# RoverWing-cover-nocut-V5.net
KiCad netlist of a schematic drawn in EAGLE
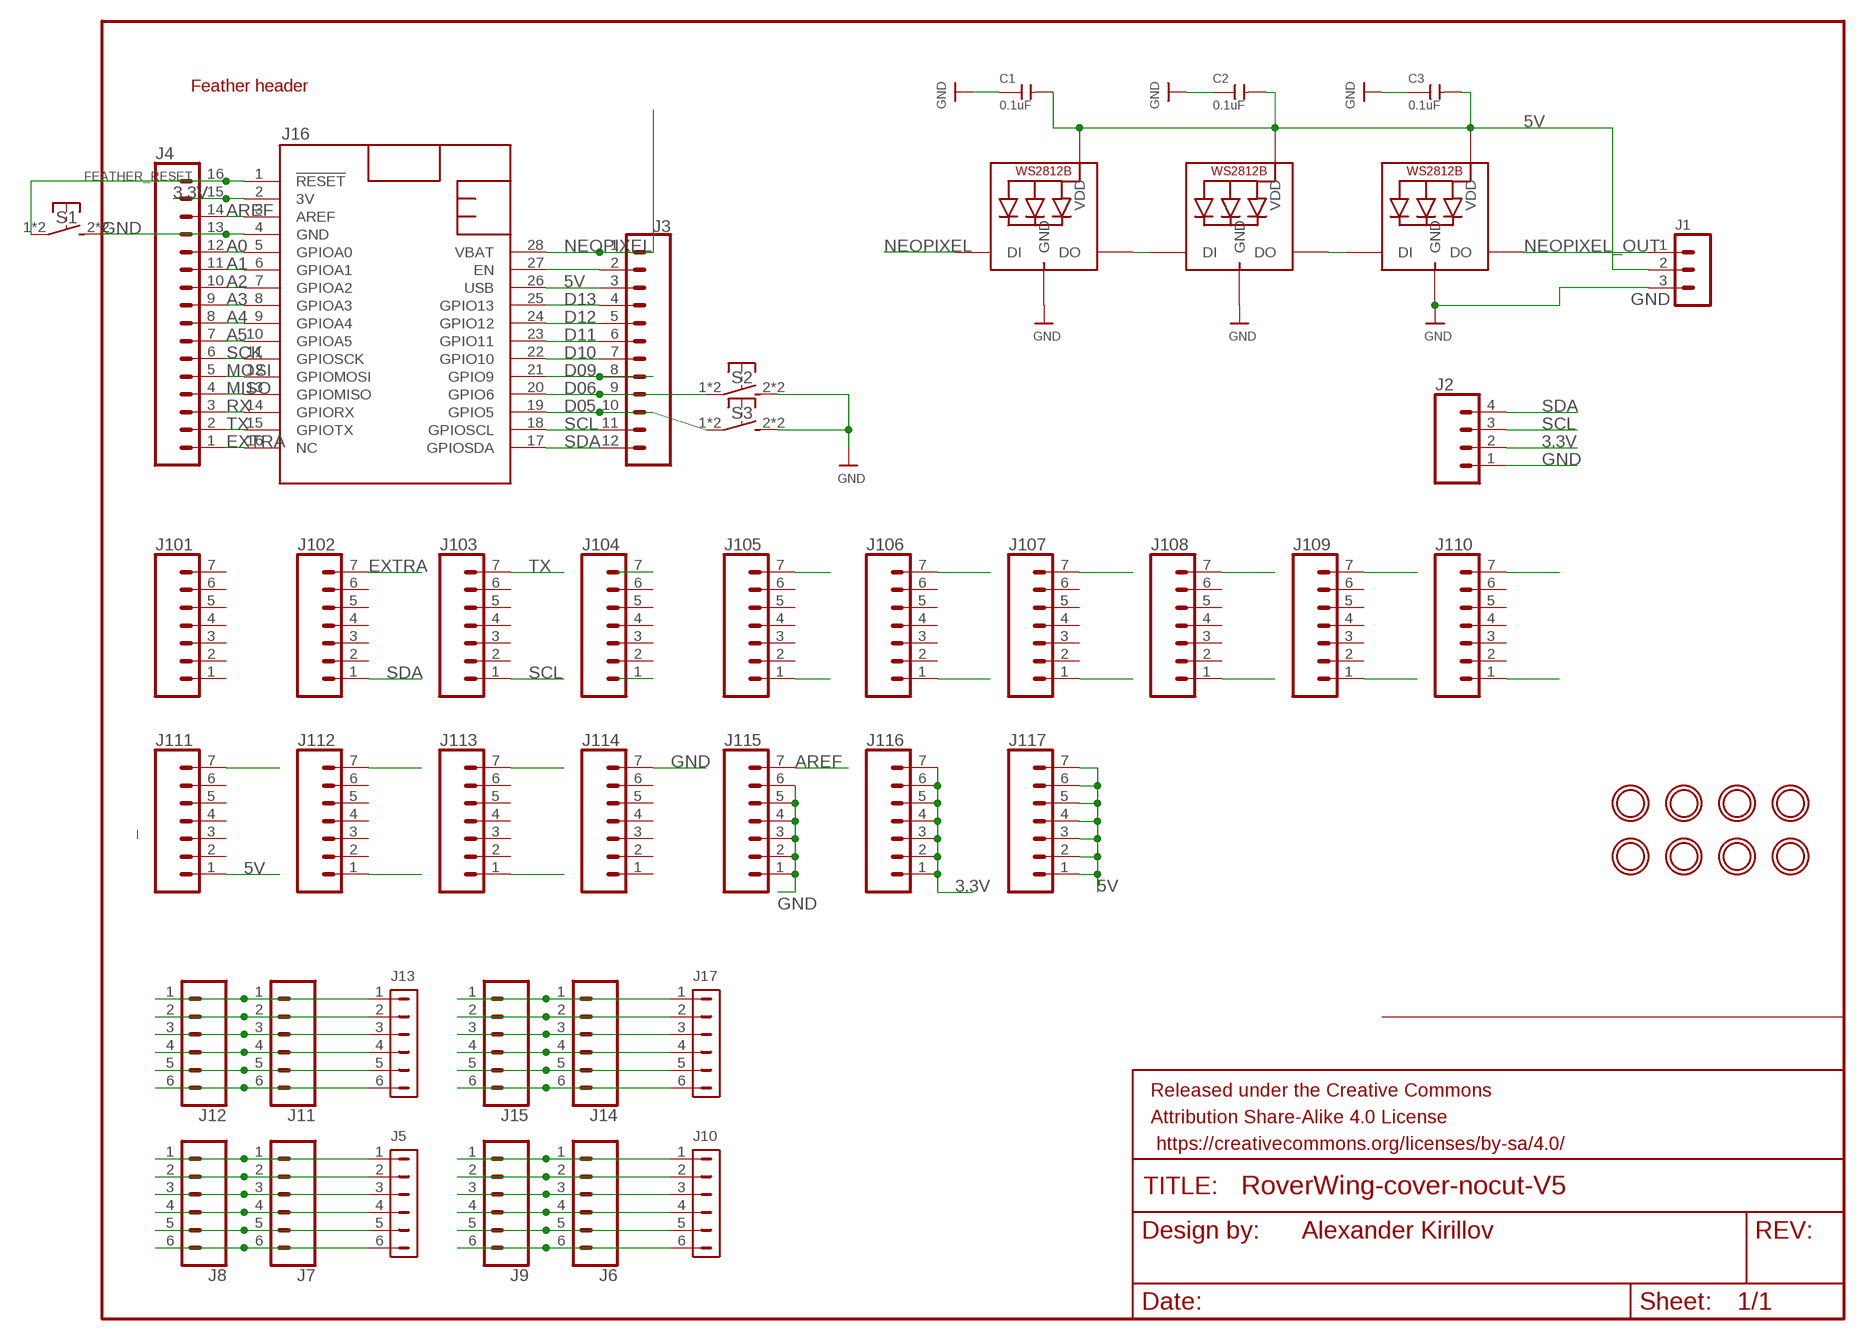
[diagram p0: schematic, sheet 1]

(export (version "E")
  (design (tool "Eeschema 10.0.6"))
  (components
    (comp (ref "C1")
      (value "0.1uF")
      (footprint "eagle-import:C0805")
      (libsource (lib "eagle-import") (part "CAP-CERAMIC-SMD-0805"))
    )
    (comp (ref "C2")
      (value "0.1uF")
      (footprint "eagle-import:C0805")
      (libsource (lib "eagle-import") (part "CAP-CERAMIC-SMD-0805"))
    )
    (comp (ref "C3")
      (value "0.1uF")
      (footprint "eagle-import:C0805")
      (libsource (lib "eagle-import") (part "CAP-CERAMIC-SMD-0805"))
    )
    (comp (ref "FRAME2")
      (value "FRAME-LETTERNO_PACKAGE")
      (footprint "eagle-import:DUMMY")
      (fields (field (name "DESIGNER") "Nobody"))
      (libsource (lib "eagle-import") (part "FRAME-LETTERNO_PACKAGE"))
    )
    (comp (ref "J1")
      (value "HEADER-PH-3PSIDEENTRY")
      (footprint "eagle-import:S3B-PH-K")
      (fields (field (name "PARTNO") "S3B-PH-K-S(LF)(SN)"))
      (libsource (lib "eagle-import") (part "HEADER-PH-3PSIDEENTRY"))
    )
    (comp (ref "J2")
      (value "CONN_04")
      (footprint "eagle-import:1X04")
      (libsource (lib "eagle-import") (part "CONN_04"))
    )
    (comp (ref "J3")
      (value "CONN_12NO_SILK")
      (footprint "eagle-import:1X12_NO_SILK")
      (libsource (lib "eagle-import") (part "CONN_12NO_SILK"))
    )
    (comp (ref "J4")
      (value "CONN_161X16_NO_SILK")
      (footprint "eagle-import:1X16_NO_SILK")
      (libsource (lib "eagle-import") (part "CONN_161X16_NO_SILK"))
    )
    (comp (ref "J5")
      (value "HEADER-PH-6PSIDEENTRY")
      (footprint "eagle-import:S6B-PH-K")
      (libsource (lib "eagle-import") (part "HEADER-PH-6PSIDEENTRY"))
    )
    (comp (ref "J6")
      (value "CONN_06NO_SILK_NO_POP")
      (footprint "eagle-import:1X06_NO_SILK")
      (libsource (lib "eagle-import") (part "CONN_06NO_SILK_NO_POP"))
    )
    (comp (ref "J7")
      (value "CONN_06NO_SILK_NO_POP")
      (footprint "eagle-import:1X06_NO_SILK")
      (libsource (lib "eagle-import") (part "CONN_06NO_SILK_NO_POP"))
    )
    (comp (ref "J8")
      (value "CONN_06NO_SILK_NO_POP")
      (footprint "eagle-import:1X06_NO_SILK")
      (libsource (lib "eagle-import") (part "CONN_06NO_SILK_NO_POP"))
    )
    (comp (ref "J9")
      (value "CONN_06NO_SILK_NO_POP")
      (footprint "eagle-import:1X06_NO_SILK")
      (libsource (lib "eagle-import") (part "CONN_06NO_SILK_NO_POP"))
    )
    (comp (ref "J10")
      (value "HEADER-PH-6PSIDEENTRY")
      (footprint "eagle-import:S6B-PH-K")
      (libsource (lib "eagle-import") (part "HEADER-PH-6PSIDEENTRY"))
    )
    (comp (ref "J11")
      (value "CONN_06NO_SILK_NO_POP")
      (footprint "eagle-import:1X06_NO_SILK")
      (libsource (lib "eagle-import") (part "CONN_06NO_SILK_NO_POP"))
    )
    (comp (ref "J12")
      (value "CONN_06NO_SILK_NO_POP")
      (footprint "eagle-import:1X06_NO_SILK")
      (libsource (lib "eagle-import") (part "CONN_06NO_SILK_NO_POP"))
    )
    (comp (ref "J13")
      (value "HEADER-PH-6PSIDEENTRY")
      (footprint "eagle-import:S6B-PH-K")
      (libsource (lib "eagle-import") (part "HEADER-PH-6PSIDEENTRY"))
    )
    (comp (ref "J14")
      (value "CONN_06NO_SILK_NO_POP")
      (footprint "eagle-import:1X06_NO_SILK")
      (libsource (lib "eagle-import") (part "CONN_06NO_SILK_NO_POP"))
    )
    (comp (ref "J15")
      (value "CONN_06NO_SILK_NO_POP")
      (footprint "eagle-import:1X06_NO_SILK")
      (libsource (lib "eagle-import") (part "CONN_06NO_SILK_NO_POP"))
    )
    (comp (ref "J16")
      (value "FEATHERWING_NODIM")
      (footprint "eagle-import:FEATHERWING_DIM")
      (libsource (lib "eagle-import") (part "FEATHERWING_NODIM"))
    )
    (comp (ref "J17")
      (value "HEADER-PH-6PSIDEENTRY")
      (footprint "eagle-import:S6B-PH-K")
      (libsource (lib "eagle-import") (part "HEADER-PH-6PSIDEENTRY"))
    )
    (comp (ref "J101")
      (value "CONN_07NO_SILK")
      (footprint "eagle-import:1X07_NO_SILK")
      (libsource (lib "eagle-import") (part "CONN_07NO_SILK"))
    )
    (comp (ref "J102")
      (value "CONN_07NO_SILK")
      (footprint "eagle-import:1X07_NO_SILK")
      (libsource (lib "eagle-import") (part "CONN_07NO_SILK"))
    )
    (comp (ref "J103")
      (value "CONN_07NO_SILK")
      (footprint "eagle-import:1X07_NO_SILK")
      (libsource (lib "eagle-import") (part "CONN_07NO_SILK"))
    )
    (comp (ref "J104")
      (value "CONN_07NO_SILK")
      (footprint "eagle-import:1X07_NO_SILK")
      (libsource (lib "eagle-import") (part "CONN_07NO_SILK"))
    )
    (comp (ref "J105")
      (value "CONN_07NO_SILK")
      (footprint "eagle-import:1X07_NO_SILK")
      (libsource (lib "eagle-import") (part "CONN_07NO_SILK"))
    )
    (comp (ref "J106")
      (value "CONN_07NO_SILK")
      (footprint "eagle-import:1X07_NO_SILK")
      (libsource (lib "eagle-import") (part "CONN_07NO_SILK"))
    )
    (comp (ref "J107")
      (value "CONN_07NO_SILK")
      (footprint "eagle-import:1X07_NO_SILK")
      (libsource (lib "eagle-import") (part "CONN_07NO_SILK"))
    )
    (comp (ref "J108")
      (value "CONN_07NO_SILK")
      (footprint "eagle-import:1X07_NO_SILK")
      (libsource (lib "eagle-import") (part "CONN_07NO_SILK"))
    )
    (comp (ref "J109")
      (value "CONN_07NO_SILK")
      (footprint "eagle-import:1X07_NO_SILK")
      (libsource (lib "eagle-import") (part "CONN_07NO_SILK"))
    )
    (comp (ref "J110")
      (value "CONN_07NO_SILK")
      (footprint "eagle-import:1X07_NO_SILK")
      (libsource (lib "eagle-import") (part "CONN_07NO_SILK"))
    )
    (comp (ref "J111")
      (value "CONN_07NO_SILK")
      (footprint "eagle-import:1X07_NO_SILK")
      (libsource (lib "eagle-import") (part "CONN_07NO_SILK"))
    )
    (comp (ref "J112")
      (value "CONN_07NO_SILK")
      (footprint "eagle-import:1X07_NO_SILK")
      (libsource (lib "eagle-import") (part "CONN_07NO_SILK"))
    )
    (comp (ref "J113")
      (value "CONN_07NO_SILK")
      (footprint "eagle-import:1X07_NO_SILK")
      (libsource (lib "eagle-import") (part "CONN_07NO_SILK"))
    )
    (comp (ref "J114")
      (value "CONN_07NO_SILK")
      (footprint "eagle-import:1X07_NO_SILK")
      (libsource (lib "eagle-import") (part "CONN_07NO_SILK"))
    )
    (comp (ref "J115")
      (value "CONN_07NO_SILK")
      (footprint "eagle-import:1X07_NO_SILK")
      (libsource (lib "eagle-import") (part "CONN_07NO_SILK"))
    )
    (comp (ref "J116")
      (value "CONN_07NO_SILK")
      (footprint "eagle-import:1X07_NO_SILK")
      (libsource (lib "eagle-import") (part "CONN_07NO_SILK"))
    )
    (comp (ref "J117")
      (value "CONN_07NO_SILK")
      (footprint "eagle-import:1X07_NO_SILK")
      (libsource (lib "eagle-import") (part "CONN_07NO_SILK"))
    )
    (comp (ref "LED1")
      (value "WS2812B5050")
      (footprint "eagle-import:WS2812B")
      (libsource (lib "eagle-import") (part "WS2812B5050"))
    )
    (comp (ref "LED2")
      (value "WS2812B5050")
      (footprint "eagle-import:WS2812B")
      (libsource (lib "eagle-import") (part "WS2812B5050"))
    )
    (comp (ref "LED3")
      (value "WS2812B5050")
      (footprint "eagle-import:WS2812B")
      (libsource (lib "eagle-import") (part "WS2812B5050"))
    )
    (comp (ref "S1")
      (value "SW-TACTILE-4.5X4.5_SMD")
      (footprint "eagle-import:TL3305")
      (libsource (lib "eagle-import") (part "SW-TACTILE-4.5X4.5_SMD"))
    )
    (comp (ref "S2")
      (value "SW-TACTILE-4.5X4.5_SMD")
      (footprint "eagle-import:TL3305")
      (libsource (lib "eagle-import") (part "SW-TACTILE-4.5X4.5_SMD"))
    )
    (comp (ref "S3")
      (value "SW-TACTILE-4.5X4.5_SMD")
      (footprint "eagle-import:TL3305")
      (libsource (lib "eagle-import") (part "SW-TACTILE-4.5X4.5_SMD"))
    )
    (comp (ref "U$3")
      (value "MOUNTINGHOLE3.0_NPH")
      (footprint "eagle-import:MOUNTINGHOLE_3.0_NPH")
      (libsource (lib "eagle-import") (part "MOUNTINGHOLE3.0_NPH"))
    )
    (comp (ref "U$4")
      (value "MOUNTINGHOLE3.0_NPH")
      (footprint "eagle-import:MOUNTINGHOLE_3.0_NPH")
      (libsource (lib "eagle-import") (part "MOUNTINGHOLE3.0_NPH"))
    )
    (comp (ref "U$14")
      (value "MOUNTINGHOLE3.0_NPH")
      (footprint "eagle-import:MOUNTINGHOLE_3.0_NPH")
      (libsource (lib "eagle-import") (part "MOUNTINGHOLE3.0_NPH"))
    )
    (comp (ref "U$15")
      (value "MOUNTINGHOLE3.0_NPH")
      (footprint "eagle-import:MOUNTINGHOLE_3.0_NPH")
      (libsource (lib "eagle-import") (part "MOUNTINGHOLE3.0_NPH"))
    )
    (comp (ref "U$24")
      (value "MOUNTINGHOLE3.0_NPH")
      (footprint "eagle-import:MOUNTINGHOLE_3.0_NPH")
      (libsource (lib "eagle-import") (part "MOUNTINGHOLE3.0_NPH"))
    )
    (comp (ref "U$25")
      (value "MOUNTINGHOLE3.0_NPH")
      (footprint "eagle-import:MOUNTINGHOLE_3.0_NPH")
      (libsource (lib "eagle-import") (part "MOUNTINGHOLE3.0_NPH"))
    )
    (comp (ref "U$26")
      (value "MOUNTINGHOLE3.0_NPH")
      (footprint "eagle-import:MOUNTINGHOLE_3.0_NPH")
      (libsource (lib "eagle-import") (part "MOUNTINGHOLE3.0_NPH"))
    )
    (comp (ref "U$27")
      (value "MOUNTINGHOLE3.0_NPH")
      (footprint "eagle-import:MOUNTINGHOLE_3.0_NPH")
      (libsource (lib "eagle-import") (part "MOUNTINGHOLE3.0_NPH"))
    )
  )
  (nets
    (net (code "1") (name "/3.3V") (class "Default")
      (node (ref "J116") (pin "1") (pinfunction "1_1") (pintype "passive"))
      (node (ref "J116") (pin "2") (pinfunction "2_2") (pintype "passive"))
      (node (ref "J116") (pin "3") (pinfunction "3_3") (pintype "passive"))
      (node (ref "J116") (pin "4") (pinfunction "4_4") (pintype "passive"))
      (node (ref "J116") (pin "5") (pinfunction "5_5") (pintype "passive"))
      (node (ref "J116") (pin "6") (pinfunction "6_6") (pintype "passive"))
      (node (ref "J116") (pin "7") (pinfunction "7_7") (pintype "passive"))
      (node (ref "J16") (pin "2") (pinfunction "3V_2") (pintype "power_in"))
      (node (ref "J2") (pin "2") (pinfunction "2_2") (pintype "passive"))
      (node (ref "J4") (pin "15") (pinfunction "15_15") (pintype "passive"))
    )
    (net (code "2") (name "/5V") (class "Default")
      (node (ref "C1") (pin "2") (pinfunction "2_2") (pintype "passive"))
      (node (ref "C2") (pin "2") (pinfunction "2_2") (pintype "passive"))
      (node (ref "C3") (pin "2") (pinfunction "2_2") (pintype "passive"))
      (node (ref "J1") (pin "2") (pinfunction "2_2") (pintype "passive"))
      (node (ref "J111") (pin "1") (pinfunction "1_1") (pintype "passive"))
      (node (ref "J117") (pin "1") (pinfunction "1_1") (pintype "passive"))
      (node (ref "J117") (pin "2") (pinfunction "2_2") (pintype "passive"))
      (node (ref "J117") (pin "3") (pinfunction "3_3") (pintype "passive"))
      (node (ref "J117") (pin "4") (pinfunction "4_4") (pintype "passive"))
      (node (ref "J117") (pin "5") (pinfunction "5_5") (pintype "passive"))
      (node (ref "J117") (pin "6") (pinfunction "6_6") (pintype "passive"))
      (node (ref "J117") (pin "7") (pinfunction "7_7") (pintype "passive"))
      (node (ref "J16") (pin "26") (pinfunction "USB_26") (pintype "power_in"))
      (node (ref "J3") (pin "3") (pinfunction "3_3") (pintype "passive"))
      (node (ref "LED1") (pin "1-VDD") (pinfunction "VDD_1-VDD") (pintype "power_in"))
      (node (ref "LED2") (pin "1-VDD") (pinfunction "VDD_1-VDD") (pintype "power_in"))
      (node (ref "LED3") (pin "1-VDD") (pinfunction "VDD_1-VDD") (pintype "power_in"))
    )
    (net (code "3") (name "/A0") (class "Default")
      (node (ref "J113") (pin "7") (pinfunction "7_7") (pintype "passive"))
      (node (ref "J16") (pin "5") (pinfunction "GPIOA0_5") (pintype "bidirectional"))
      (node (ref "J4") (pin "12") (pinfunction "12_12") (pintype "passive"))
    )
    (net (code "4") (name "/A1") (class "Default")
      (node (ref "J112") (pin "7") (pinfunction "7_7") (pintype "passive"))
      (node (ref "J16") (pin "6") (pinfunction "GPIOA1_6") (pintype "bidirectional"))
      (node (ref "J4") (pin "11") (pinfunction "11_11") (pintype "passive"))
    )
    (net (code "5") (name "/A2") (class "Default")
      (node (ref "J111") (pin "7") (pinfunction "7_7") (pintype "passive"))
      (node (ref "J16") (pin "7") (pinfunction "GPIOA2_7") (pintype "bidirectional"))
      (node (ref "J4") (pin "10") (pinfunction "10_10") (pintype "passive"))
    )
    (net (code "6") (name "/A3") (class "Default")
      (node (ref "J110") (pin "7") (pinfunction "7_7") (pintype "passive"))
      (node (ref "J16") (pin "8") (pinfunction "GPIOA3_8") (pintype "bidirectional"))
      (node (ref "J4") (pin "9") (pinfunction "9_9") (pintype "passive"))
    )
    (net (code "7") (name "/A4") (class "Default")
      (node (ref "J109") (pin "7") (pinfunction "7_7") (pintype "passive"))
      (node (ref "J16") (pin "9") (pinfunction "GPIOA4_9") (pintype "bidirectional"))
      (node (ref "J4") (pin "8") (pinfunction "8_8") (pintype "passive"))
    )
    (net (code "8") (name "/A5") (class "Default")
      (node (ref "J108") (pin "7") (pinfunction "7_7") (pintype "passive"))
      (node (ref "J16") (pin "10") (pinfunction "GPIOA5_10") (pintype "bidirectional"))
      (node (ref "J4") (pin "7") (pinfunction "7_7") (pintype "passive"))
    )
    (net (code "9") (name "/AREF") (class "Default")
      (node (ref "J115") (pin "7") (pinfunction "7_7") (pintype "passive"))
      (node (ref "J16") (pin "3") (pinfunction "AREF_3") (pintype "passive"))
      (node (ref "J4") (pin "14") (pinfunction "14_14") (pintype "passive"))
    )
    (net (code "10") (name "/D05") (class "Default")
      (node (ref "J104") (pin "1") (pinfunction "1_1") (pintype "passive"))
      (node (ref "J16") (pin "19") (pinfunction "GPIO5_19") (pintype "bidirectional"))
      (node (ref "J3") (pin "10") (pinfunction "10_10") (pintype "passive"))
      (node (ref "S3") (pin "1") (pinfunction "P1_1") (pintype "passive"))
      (node (ref "S3") (pin "4") (pinfunction "P1_4") (pintype "passive"))
    )
    (net (code "11") (name "/D06") (class "Default")
      (node (ref "J105") (pin "1") (pinfunction "1_1") (pintype "passive"))
      (node (ref "J16") (pin "20") (pinfunction "GPIO6_20") (pintype "bidirectional"))
      (node (ref "J3") (pin "9") (pinfunction "9_9") (pintype "passive"))
      (node (ref "S2") (pin "1") (pinfunction "P1_1") (pintype "passive"))
      (node (ref "S2") (pin "4") (pinfunction "P1_4") (pintype "passive"))
    )
    (net (code "12") (name "/D09") (class "Default")
      (node (ref "J106") (pin "1") (pinfunction "1_1") (pintype "passive"))
      (node (ref "J16") (pin "21") (pinfunction "GPIO9_21") (pintype "bidirectional"))
      (node (ref "J3") (pin "8") (pinfunction "8_8") (pintype "passive"))
    )
    (net (code "13") (name "/D10") (class "Default")
      (node (ref "J107") (pin "1") (pinfunction "1_1") (pintype "passive"))
      (node (ref "J16") (pin "22") (pinfunction "GPIO10_22") (pintype "bidirectional"))
      (node (ref "J3") (pin "7") (pinfunction "7_7") (pintype "passive"))
    )
    (net (code "14") (name "/D11") (class "Default")
      (node (ref "J108") (pin "1") (pinfunction "1_1") (pintype "passive"))
      (node (ref "J16") (pin "23") (pinfunction "GPIO11_23") (pintype "bidirectional"))
      (node (ref "J3") (pin "6") (pinfunction "6_6") (pintype "passive"))
    )
    (net (code "15") (name "/D12") (class "Default")
      (node (ref "J109") (pin "1") (pinfunction "1_1") (pintype "passive"))
      (node (ref "J16") (pin "24") (pinfunction "GPIO12_24") (pintype "bidirectional"))
      (node (ref "J3") (pin "5") (pinfunction "5_5") (pintype "passive"))
    )
    (net (code "16") (name "/D13") (class "Default")
      (node (ref "J110") (pin "1") (pinfunction "1_1") (pintype "passive"))
      (node (ref "J16") (pin "25") (pinfunction "GPIO13_25") (pintype "bidirectional"))
      (node (ref "J3") (pin "4") (pinfunction "4_4") (pintype "passive"))
    )
    (net (code "17") (name "/EXTRA") (class "Default")
      (node (ref "J102") (pin "7") (pinfunction "7_7") (pintype "passive"))
      (node (ref "J16") (pin "16") (pinfunction "NC_16") (pintype "passive"))
      (node (ref "J4") (pin "1") (pinfunction "1_1") (pintype "passive"))
    )
    (net (code "18") (name "/FEATHER_RESET") (class "Default")
      (node (ref "J16") (pin "1") (pinfunction "~{RESET}_1") (pintype "input"))
      (node (ref "J4") (pin "16") (pinfunction "16_16") (pintype "passive"))
      (node (ref "S1") (pin "1") (pinfunction "P1_1") (pintype "passive"))
      (node (ref "S1") (pin "4") (pinfunction "P1_4") (pintype "passive"))
    )
    (net (code "19") (name "/MISO") (class "Default")
      (node (ref "J105") (pin "7") (pinfunction "7_7") (pintype "passive"))
      (node (ref "J16") (pin "13") (pinfunction "GPIOMISO_13") (pintype "bidirectional"))
      (node (ref "J4") (pin "4") (pinfunction "4_4") (pintype "passive"))
    )
    (net (code "20") (name "/MOSI") (class "Default")
      (node (ref "J106") (pin "7") (pinfunction "7_7") (pintype "passive"))
      (node (ref "J16") (pin "12") (pinfunction "GPIOMOSI_12") (pintype "bidirectional"))
      (node (ref "J4") (pin "5") (pinfunction "5_5") (pintype "passive"))
    )
    (net (code "21") (name "/N$37") (class "Default")
      (node (ref "J112") (pin "1") (pinfunction "1_1") (pintype "passive"))
      (node (ref "J16") (pin "27") (pinfunction "EN_27") (pintype "passive"))
      (node (ref "J3") (pin "2") (pinfunction "2_2") (pintype "passive"))
    )
    (net (code "22") (name "/NEOPIXEL") (class "Default")
      (node (ref "J16") (pin "28") (pinfunction "VBAT_28") (pintype "power_in"))
      (node (ref "J3") (pin "1") (pinfunction "1_1") (pintype "passive"))
      (node (ref "LED1") (pin "4-DIN") (pinfunction "DI_4-DIN") (pintype "input"))
    )
    (net (code "23") (name "/NEOPIXEL_OUT") (class "Default")
      (node (ref "J1") (pin "1") (pinfunction "1_1") (pintype "passive"))
      (node (ref "LED3") (pin "2-DOUT") (pinfunction "DO_2-DOUT") (pintype "output"))
    )
    (net (code "24") (name "/RX") (class "Default")
      (node (ref "J104") (pin "7") (pinfunction "7_7") (pintype "passive"))
      (node (ref "J16") (pin "14") (pinfunction "GPIORX_14") (pintype "bidirectional"))
      (node (ref "J4") (pin "3") (pinfunction "3_3") (pintype "passive"))
    )
    (net (code "25") (name "/SCK") (class "Default")
      (node (ref "J107") (pin "7") (pinfunction "7_7") (pintype "passive"))
      (node (ref "J16") (pin "11") (pinfunction "GPIOSCK_11") (pintype "bidirectional"))
      (node (ref "J4") (pin "6") (pinfunction "6_6") (pintype "passive"))
    )
    (net (code "26") (name "/SCL") (class "Default")
      (node (ref "J103") (pin "1") (pinfunction "1_1") (pintype "passive"))
      (node (ref "J16") (pin "18") (pinfunction "GPIOSCL_18") (pintype "bidirectional"))
      (node (ref "J2") (pin "3") (pinfunction "3_3") (pintype "passive"))
      (node (ref "J3") (pin "11") (pinfunction "11_11") (pintype "passive"))
    )
    (net (code "27") (name "/SDA") (class "Default")
      (node (ref "J102") (pin "1") (pinfunction "1_1") (pintype "passive"))
      (node (ref "J16") (pin "17") (pinfunction "GPIOSDA_17") (pintype "bidirectional"))
      (node (ref "J2") (pin "4") (pinfunction "4_4") (pintype "passive"))
      (node (ref "J3") (pin "12") (pinfunction "12_12") (pintype "passive"))
    )
    (net (code "28") (name "/TX") (class "Default")
      (node (ref "J103") (pin "7") (pinfunction "7_7") (pintype "passive"))
      (node (ref "J16") (pin "15") (pinfunction "GPIOTX_15") (pintype "bidirectional"))
      (node (ref "J4") (pin "2") (pinfunction "2_2") (pintype "passive"))
    )
    (net (code "29") (name "GND") (class "Default")
      (node (ref "C1") (pin "1") (pinfunction "1_1") (pintype "passive"))
      (node (ref "C2") (pin "1") (pinfunction "1_1") (pintype "passive"))
      (node (ref "C3") (pin "1") (pinfunction "1_1") (pintype "passive"))
      (node (ref "J1") (pin "3") (pinfunction "3_3") (pintype "passive"))
      (node (ref "J114") (pin "7") (pinfunction "7_7") (pintype "passive"))
      (node (ref "J115") (pin "1") (pinfunction "1_1") (pintype "passive"))
      (node (ref "J115") (pin "2") (pinfunction "2_2") (pintype "passive"))
      (node (ref "J115") (pin "3") (pinfunction "3_3") (pintype "passive"))
      (node (ref "J115") (pin "4") (pinfunction "4_4") (pintype "passive"))
      (node (ref "J115") (pin "5") (pinfunction "5_5") (pintype "passive"))
      (node (ref "J115") (pin "6") (pinfunction "6_6") (pintype "passive"))
      (node (ref "J16") (pin "4") (pinfunction "GND_4") (pintype "power_in"))
      (node (ref "J2") (pin "1") (pinfunction "1_1") (pintype "passive"))
      (node (ref "J4") (pin "13") (pinfunction "13_13") (pintype "passive"))
      (node (ref "LED1") (pin "3-GND") (pinfunction "GND_3-GND") (pintype "power_in"))
      (node (ref "LED2") (pin "3-GND") (pinfunction "GND_3-GND") (pintype "power_in"))
      (node (ref "LED3") (pin "3-GND") (pinfunction "GND_3-GND") (pintype "power_in"))
      (node (ref "S1") (pin "2") (pinfunction "S1_2") (pintype "passive"))
      (node (ref "S1") (pin "3") (pinfunction "S1_3") (pintype "passive"))
      (node (ref "S2") (pin "2") (pinfunction "S1_2") (pintype "passive"))
      (node (ref "S2") (pin "3") (pinfunction "S1_3") (pintype "passive"))
      (node (ref "S3") (pin "2") (pinfunction "S1_2") (pintype "passive"))
      (node (ref "S3") (pin "3") (pinfunction "S1_3") (pintype "passive"))
    )
    (net (code "30") (name "Net-(J5-Pad1)") (class "Default")
      (node (ref "J5") (pin "1") (pinfunction "1_1") (pintype "passive"))
      (node (ref "J7") (pin "1") (pinfunction "1_1") (pintype "passive"))
      (node (ref "J8") (pin "1") (pinfunction "1_1") (pintype "passive"))
    )
    (net (code "31") (name "Net-(J5-Pad2)") (class "Default")
      (node (ref "J5") (pin "2") (pinfunction "2_2") (pintype "passive"))
      (node (ref "J7") (pin "2") (pinfunction "2_2") (pintype "passive"))
      (node (ref "J8") (pin "2") (pinfunction "2_2") (pintype "passive"))
    )
    (net (code "32") (name "Net-(J5-Pad3)") (class "Default")
      (node (ref "J5") (pin "3") (pinfunction "3_3") (pintype "passive"))
      (node (ref "J7") (pin "3") (pinfunction "3_3") (pintype "passive"))
      (node (ref "J8") (pin "3") (pinfunction "3_3") (pintype "passive"))
    )
    (net (code "33") (name "Net-(J5-Pad4)") (class "Default")
      (node (ref "J5") (pin "4") (pinfunction "4_4") (pintype "passive"))
      (node (ref "J7") (pin "4") (pinfunction "4_4") (pintype "passive"))
      (node (ref "J8") (pin "4") (pinfunction "4_4") (pintype "passive"))
    )
    (net (code "34") (name "Net-(J5-Pad5)") (class "Default")
      (node (ref "J5") (pin "5") (pinfunction "5_5") (pintype "passive"))
      (node (ref "J7") (pin "5") (pinfunction "5_5") (pintype "passive"))
      (node (ref "J8") (pin "5") (pinfunction "5_5") (pintype "passive"))
    )
    (net (code "35") (name "Net-(J5-Pad6)") (class "Default")
      (node (ref "J5") (pin "6") (pinfunction "6_6") (pintype "passive"))
      (node (ref "J7") (pin "6") (pinfunction "6_6") (pintype "passive"))
      (node (ref "J8") (pin "6") (pinfunction "6_6") (pintype "passive"))
    )
    (net (code "36") (name "Net-(J10-Pad1)") (class "Default")
      (node (ref "J10") (pin "1") (pinfunction "1_1") (pintype "passive"))
      (node (ref "J6") (pin "1") (pinfunction "1_1") (pintype "passive"))
      (node (ref "J9") (pin "1") (pinfunction "1_1") (pintype "passive"))
    )
    (net (code "37") (name "Net-(J10-Pad2)") (class "Default")
      (node (ref "J10") (pin "2") (pinfunction "2_2") (pintype "passive"))
      (node (ref "J6") (pin "2") (pinfunction "2_2") (pintype "passive"))
      (node (ref "J9") (pin "2") (pinfunction "2_2") (pintype "passive"))
    )
    (net (code "38") (name "Net-(J10-Pad3)") (class "Default")
      (node (ref "J10") (pin "3") (pinfunction "3_3") (pintype "passive"))
      (node (ref "J6") (pin "3") (pinfunction "3_3") (pintype "passive"))
      (node (ref "J9") (pin "3") (pinfunction "3_3") (pintype "passive"))
    )
    (net (code "39") (name "Net-(J10-Pad4)") (class "Default")
      (node (ref "J10") (pin "4") (pinfunction "4_4") (pintype "passive"))
      (node (ref "J6") (pin "4") (pinfunction "4_4") (pintype "passive"))
      (node (ref "J9") (pin "4") (pinfunction "4_4") (pintype "passive"))
    )
    (net (code "40") (name "Net-(J10-Pad5)") (class "Default")
      (node (ref "J10") (pin "5") (pinfunction "5_5") (pintype "passive"))
      (node (ref "J6") (pin "5") (pinfunction "5_5") (pintype "passive"))
      (node (ref "J9") (pin "5") (pinfunction "5_5") (pintype "passive"))
    )
    (net (code "41") (name "Net-(J10-Pad6)") (class "Default")
      (node (ref "J10") (pin "6") (pinfunction "6_6") (pintype "passive"))
      (node (ref "J6") (pin "6") (pinfunction "6_6") (pintype "passive"))
      (node (ref "J9") (pin "6") (pinfunction "6_6") (pintype "passive"))
    )
    (net (code "42") (name "Net-(J11-Pad1)") (class "Default")
      (node (ref "J11") (pin "1") (pinfunction "1_1") (pintype "passive"))
      (node (ref "J12") (pin "1") (pinfunction "1_1") (pintype "passive"))
      (node (ref "J13") (pin "1") (pinfunction "1_1") (pintype "passive"))
    )
    (net (code "43") (name "Net-(J11-Pad2)") (class "Default")
      (node (ref "J11") (pin "2") (pinfunction "2_2") (pintype "passive"))
      (node (ref "J12") (pin "2") (pinfunction "2_2") (pintype "passive"))
      (node (ref "J13") (pin "2") (pinfunction "2_2") (pintype "passive"))
    )
    (net (code "44") (name "Net-(J11-Pad3)") (class "Default")
      (node (ref "J11") (pin "3") (pinfunction "3_3") (pintype "passive"))
      (node (ref "J12") (pin "3") (pinfunction "3_3") (pintype "passive"))
      (node (ref "J13") (pin "3") (pinfunction "3_3") (pintype "passive"))
    )
    (net (code "45") (name "Net-(J11-Pad4)") (class "Default")
      (node (ref "J11") (pin "4") (pinfunction "4_4") (pintype "passive"))
      (node (ref "J12") (pin "4") (pinfunction "4_4") (pintype "passive"))
      (node (ref "J13") (pin "4") (pinfunction "4_4") (pintype "passive"))
    )
    (net (code "46") (name "Net-(J11-Pad5)") (class "Default")
      (node (ref "J11") (pin "5") (pinfunction "5_5") (pintype "passive"))
      (node (ref "J12") (pin "5") (pinfunction "5_5") (pintype "passive"))
      (node (ref "J13") (pin "5") (pinfunction "5_5") (pintype "passive"))
    )
    (net (code "47") (name "Net-(J11-Pad6)") (class "Default")
      (node (ref "J11") (pin "6") (pinfunction "6_6") (pintype "passive"))
      (node (ref "J12") (pin "6") (pinfunction "6_6") (pintype "passive"))
      (node (ref "J13") (pin "6") (pinfunction "6_6") (pintype "passive"))
    )
    (net (code "48") (name "Net-(J14-Pad1)") (class "Default")
      (node (ref "J14") (pin "1") (pinfunction "1_1") (pintype "passive"))
      (node (ref "J15") (pin "1") (pinfunction "1_1") (pintype "passive"))
      (node (ref "J17") (pin "1") (pinfunction "1_1") (pintype "passive"))
    )
    (net (code "49") (name "Net-(J14-Pad2)") (class "Default")
      (node (ref "J14") (pin "2") (pinfunction "2_2") (pintype "passive"))
      (node (ref "J15") (pin "2") (pinfunction "2_2") (pintype "passive"))
      (node (ref "J17") (pin "2") (pinfunction "2_2") (pintype "passive"))
    )
    (net (code "50") (name "Net-(J14-Pad3)") (class "Default")
      (node (ref "J14") (pin "3") (pinfunction "3_3") (pintype "passive"))
      (node (ref "J15") (pin "3") (pinfunction "3_3") (pintype "passive"))
      (node (ref "J17") (pin "3") (pinfunction "3_3") (pintype "passive"))
    )
    (net (code "51") (name "Net-(J14-Pad4)") (class "Default")
      (node (ref "J14") (pin "4") (pinfunction "4_4") (pintype "passive"))
      (node (ref "J15") (pin "4") (pinfunction "4_4") (pintype "passive"))
      (node (ref "J17") (pin "4") (pinfunction "4_4") (pintype "passive"))
    )
    (net (code "52") (name "Net-(J14-Pad5)") (class "Default")
      (node (ref "J14") (pin "5") (pinfunction "5_5") (pintype "passive"))
      (node (ref "J15") (pin "5") (pinfunction "5_5") (pintype "passive"))
      (node (ref "J17") (pin "5") (pinfunction "5_5") (pintype "passive"))
    )
    (net (code "53") (name "Net-(J14-Pad6)") (class "Default")
      (node (ref "J14") (pin "6") (pinfunction "6_6") (pintype "passive"))
      (node (ref "J15") (pin "6") (pinfunction "6_6") (pintype "passive"))
      (node (ref "J17") (pin "6") (pinfunction "6_6") (pintype "passive"))
    )
    (net (code "54") (name "Net-(LED1-DO)") (class "Default")
      (node (ref "LED1") (pin "2-DOUT") (pinfunction "DO_2-DOUT") (pintype "output"))
      (node (ref "LED2") (pin "4-DIN") (pinfunction "DI_4-DIN") (pintype "input"))
    )
    (net (code "55") (name "Net-(LED2-DO)") (class "Default")
      (node (ref "LED2") (pin "2-DOUT") (pinfunction "DO_2-DOUT") (pintype "output"))
      (node (ref "LED3") (pin "4-DIN") (pinfunction "DI_4-DIN") (pintype "input"))
    )
    (net (code "56") (name "unconnected-(J101-Pad1)") (class "Default")
      (node (ref "J101") (pin "1") (pinfunction "1_1") (pintype "passive"))
    )
    (net (code "57") (name "unconnected-(J101-Pad2)") (class "Default")
      (node (ref "J101") (pin "2") (pinfunction "2_2") (pintype "passive"))
    )
    (net (code "58") (name "unconnected-(J101-Pad3)") (class "Default")
      (node (ref "J101") (pin "3") (pinfunction "3_3") (pintype "passive"))
    )
    (net (code "59") (name "unconnected-(J101-Pad4)") (class "Default")
      (node (ref "J101") (pin "4") (pinfunction "4_4") (pintype "passive"))
    )
    (net (code "60") (name "unconnected-(J101-Pad5)") (class "Default")
      (node (ref "J101") (pin "5") (pinfunction "5_5") (pintype "passive"))
    )
    (net (code "61") (name "unconnected-(J101-Pad6)") (class "Default")
      (node (ref "J101") (pin "6") (pinfunction "6_6") (pintype "passive"))
    )
    (net (code "62") (name "unconnected-(J101-Pad7)") (class "Default")
      (node (ref "J101") (pin "7") (pinfunction "7_7") (pintype "passive"))
    )
    (net (code "63") (name "unconnected-(J102-Pad2)") (class "Default")
      (node (ref "J102") (pin "2") (pinfunction "2_2") (pintype "passive"))
    )
    (net (code "64") (name "unconnected-(J102-Pad3)") (class "Default")
      (node (ref "J102") (pin "3") (pinfunction "3_3") (pintype "passive"))
    )
    (net (code "65") (name "unconnected-(J102-Pad4)") (class "Default")
      (node (ref "J102") (pin "4") (pinfunction "4_4") (pintype "passive"))
    )
    (net (code "66") (name "unconnected-(J102-Pad5)") (class "Default")
      (node (ref "J102") (pin "5") (pinfunction "5_5") (pintype "passive"))
    )
    (net (code "67") (name "unconnected-(J102-Pad6)") (class "Default")
      (node (ref "J102") (pin "6") (pinfunction "6_6") (pintype "passive"))
    )
    (net (code "68") (name "unconnected-(J103-Pad2)") (class "Default")
      (node (ref "J103") (pin "2") (pinfunction "2_2") (pintype "passive"))
    )
    (net (code "69") (name "unconnected-(J103-Pad3)") (class "Default")
      (node (ref "J103") (pin "3") (pinfunction "3_3") (pintype "passive"))
    )
    (net (code "70") (name "unconnected-(J103-Pad4)") (class "Default")
      (node (ref "J103") (pin "4") (pinfunction "4_4") (pintype "passive"))
    )
    (net (code "71") (name "unconnected-(J103-Pad5)") (class "Default")
      (node (ref "J103") (pin "5") (pinfunction "5_5") (pintype "passive"))
    )
    (net (code "72") (name "unconnected-(J103-Pad6)") (class "Default")
      (node (ref "J103") (pin "6") (pinfunction "6_6") (pintype "passive"))
    )
    (net (code "73") (name "unconnected-(J104-Pad2)") (class "Default")
      (node (ref "J104") (pin "2") (pinfunction "2_2") (pintype "passive"))
    )
    (net (code "74") (name "unconnected-(J104-Pad3)") (class "Default")
      (node (ref "J104") (pin "3") (pinfunction "3_3") (pintype "passive"))
    )
    (net (code "75") (name "unconnected-(J104-Pad4)") (class "Default")
      (node (ref "J104") (pin "4") (pinfunction "4_4") (pintype "passive"))
    )
    (net (code "76") (name "unconnected-(J104-Pad5)") (class "Default")
      (node (ref "J104") (pin "5") (pinfunction "5_5") (pintype "passive"))
    )
    (net (code "77") (name "unconnected-(J104-Pad6)") (class "Default")
      (node (ref "J104") (pin "6") (pinfunction "6_6") (pintype "passive"))
    )
    (net (code "78") (name "unconnected-(J105-Pad2)") (class "Default")
      (node (ref "J105") (pin "2") (pinfunction "2_2") (pintype "passive"))
    )
    (net (code "79") (name "unconnected-(J105-Pad3)") (class "Default")
      (node (ref "J105") (pin "3") (pinfunction "3_3") (pintype "passive"))
    )
    (net (code "80") (name "unconnected-(J105-Pad4)") (class "Default")
      (node (ref "J105") (pin "4") (pinfunction "4_4") (pintype "passive"))
    )
    (net (code "81") (name "unconnected-(J105-Pad5)") (class "Default")
      (node (ref "J105") (pin "5") (pinfunction "5_5") (pintype "passive"))
    )
    (net (code "82") (name "unconnected-(J105-Pad6)") (class "Default")
      (node (ref "J105") (pin "6") (pinfunction "6_6") (pintype "passive"))
    )
    (net (code "83") (name "unconnected-(J106-Pad2)") (class "Default")
      (node (ref "J106") (pin "2") (pinfunction "2_2") (pintype "passive"))
    )
    (net (code "84") (name "unconnected-(J106-Pad3)") (class "Default")
      (node (ref "J106") (pin "3") (pinfunction "3_3") (pintype "passive"))
    )
    (net (code "85") (name "unconnected-(J106-Pad4)") (class "Default")
      (node (ref "J106") (pin "4") (pinfunction "4_4") (pintype "passive"))
    )
    (net (code "86") (name "unconnected-(J106-Pad5)") (class "Default")
      (node (ref "J106") (pin "5") (pinfunction "5_5") (pintype "passive"))
    )
    (net (code "87") (name "unconnected-(J106-Pad6)") (class "Default")
      (node (ref "J106") (pin "6") (pinfunction "6_6") (pintype "passive"))
    )
    (net (code "88") (name "unconnected-(J107-Pad2)") (class "Default")
      (node (ref "J107") (pin "2") (pinfunction "2_2") (pintype "passive"))
    )
    (net (code "89") (name "unconnected-(J107-Pad3)") (class "Default")
      (node (ref "J107") (pin "3") (pinfunction "3_3") (pintype "passive"))
    )
    (net (code "90") (name "unconnected-(J107-Pad4)") (class "Default")
      (node (ref "J107") (pin "4") (pinfunction "4_4") (pintype "passive"))
    )
    (net (code "91") (name "unconnected-(J107-Pad5)") (class "Default")
      (node (ref "J107") (pin "5") (pinfunction "5_5") (pintype "passive"))
    )
    (net (code "92") (name "unconnected-(J107-Pad6)") (class "Default")
      (node (ref "J107") (pin "6") (pinfunction "6_6") (pintype "passive"))
    )
    (net (code "93") (name "unconnected-(J108-Pad2)") (class "Default")
      (node (ref "J108") (pin "2") (pinfunction "2_2") (pintype "passive"))
    )
    (net (code "94") (name "unconnected-(J108-Pad3)") (class "Default")
      (node (ref "J108") (pin "3") (pinfunction "3_3") (pintype "passive"))
    )
    (net (code "95") (name "unconnected-(J108-Pad4)") (class "Default")
      (node (ref "J108") (pin "4") (pinfunction "4_4") (pintype "passive"))
    )
    (net (code "96") (name "unconnected-(J108-Pad5)") (class "Default")
      (node (ref "J108") (pin "5") (pinfunction "5_5") (pintype "passive"))
    )
    (net (code "97") (name "unconnected-(J108-Pad6)") (class "Default")
      (node (ref "J108") (pin "6") (pinfunction "6_6") (pintype "passive"))
    )
    (net (code "98") (name "unconnected-(J109-Pad2)") (class "Default")
      (node (ref "J109") (pin "2") (pinfunction "2_2") (pintype "passive"))
    )
    (net (code "99") (name "unconnected-(J109-Pad3)") (class "Default")
      (node (ref "J109") (pin "3") (pinfunction "3_3") (pintype "passive"))
    )
    (net (code "100") (name "unconnected-(J109-Pad4)") (class "Default")
      (node (ref "J109") (pin "4") (pinfunction "4_4") (pintype "passive"))
    )
    (net (code "101") (name "unconnected-(J109-Pad5)") (class "Default")
      (node (ref "J109") (pin "5") (pinfunction "5_5") (pintype "passive"))
    )
    (net (code "102") (name "unconnected-(J109-Pad6)") (class "Default")
      (node (ref "J109") (pin "6") (pinfunction "6_6") (pintype "passive"))
    )
    (net (code "103") (name "unconnected-(J110-Pad2)") (class "Default")
      (node (ref "J110") (pin "2") (pinfunction "2_2") (pintype "passive"))
    )
    (net (code "104") (name "unconnected-(J110-Pad3)") (class "Default")
      (node (ref "J110") (pin "3") (pinfunction "3_3") (pintype "passive"))
    )
    (net (code "105") (name "unconnected-(J110-Pad4)") (class "Default")
      (node (ref "J110") (pin "4") (pinfunction "4_4") (pintype "passive"))
    )
    (net (code "106") (name "unconnected-(J110-Pad5)") (class "Default")
      (node (ref "J110") (pin "5") (pinfunction "5_5") (pintype "passive"))
    )
    (net (code "107") (name "unconnected-(J110-Pad6)") (class "Default")
      (node (ref "J110") (pin "6") (pinfunction "6_6") (pintype "passive"))
    )
    (net (code "108") (name "unconnected-(J111-Pad2)") (class "Default")
      (node (ref "J111") (pin "2") (pinfunction "2_2") (pintype "passive"))
    )
    (net (code "109") (name "unconnected-(J111-Pad3)") (class "Default")
      (node (ref "J111") (pin "3") (pinfunction "3_3") (pintype "passive"))
    )
    (net (code "110") (name "unconnected-(J111-Pad4)") (class "Default")
      (node (ref "J111") (pin "4") (pinfunction "4_4") (pintype "passive"))
    )
    (net (code "111") (name "unconnected-(J111-Pad5)") (class "Default")
      (node (ref "J111") (pin "5") (pinfunction "5_5") (pintype "passive"))
    )
    (net (code "112") (name "unconnected-(J111-Pad6)") (class "Default")
      (node (ref "J111") (pin "6") (pinfunction "6_6") (pintype "passive"))
    )
    (net (code "113") (name "unconnected-(J112-Pad2)") (class "Default")
      (node (ref "J112") (pin "2") (pinfunction "2_2") (pintype "passive"))
    )
    (net (code "114") (name "unconnected-(J112-Pad3)") (class "Default")
      (node (ref "J112") (pin "3") (pinfunction "3_3") (pintype "passive"))
    )
    (net (code "115") (name "unconnected-(J112-Pad4)") (class "Default")
      (node (ref "J112") (pin "4") (pinfunction "4_4") (pintype "passive"))
    )
    (net (code "116") (name "unconnected-(J112-Pad5)") (class "Default")
      (node (ref "J112") (pin "5") (pinfunction "5_5") (pintype "passive"))
    )
    (net (code "117") (name "unconnected-(J112-Pad6)") (class "Default")
      (node (ref "J112") (pin "6") (pinfunction "6_6") (pintype "passive"))
    )
    (net (code "118") (name "unconnected-(J113-Pad1)") (class "Default")
      (node (ref "J113") (pin "1") (pinfunction "1_1") (pintype "passive"))
    )
    (net (code "119") (name "unconnected-(J113-Pad2)") (class "Default")
      (node (ref "J113") (pin "2") (pinfunction "2_2") (pintype "passive"))
    )
    (net (code "120") (name "unconnected-(J113-Pad3)") (class "Default")
      (node (ref "J113") (pin "3") (pinfunction "3_3") (pintype "passive"))
    )
    (net (code "121") (name "unconnected-(J113-Pad4)") (class "Default")
      (node (ref "J113") (pin "4") (pinfunction "4_4") (pintype "passive"))
    )
    (net (code "122") (name "unconnected-(J113-Pad5)") (class "Default")
      (node (ref "J113") (pin "5") (pinfunction "5_5") (pintype "passive"))
    )
    (net (code "123") (name "unconnected-(J113-Pad6)") (class "Default")
      (node (ref "J113") (pin "6") (pinfunction "6_6") (pintype "passive"))
    )
    (net (code "124") (name "unconnected-(J114-Pad1)") (class "Default")
      (node (ref "J114") (pin "1") (pinfunction "1_1") (pintype "passive"))
    )
    (net (code "125") (name "unconnected-(J114-Pad2)") (class "Default")
      (node (ref "J114") (pin "2") (pinfunction "2_2") (pintype "passive"))
    )
    (net (code "126") (name "unconnected-(J114-Pad3)") (class "Default")
      (node (ref "J114") (pin "3") (pinfunction "3_3") (pintype "passive"))
    )
    (net (code "127") (name "unconnected-(J114-Pad4)") (class "Default")
      (node (ref "J114") (pin "4") (pinfunction "4_4") (pintype "passive"))
    )
    (net (code "128") (name "unconnected-(J114-Pad5)") (class "Default")
      (node (ref "J114") (pin "5") (pinfunction "5_5") (pintype "passive"))
    )
    (net (code "129") (name "unconnected-(J114-Pad6)") (class "Default")
      (node (ref "J114") (pin "6") (pinfunction "6_6") (pintype "passive"))
    )
  )
)
